# 6v_BOOST.net
KiCad netlist of a schematic drawn in Altium Designer
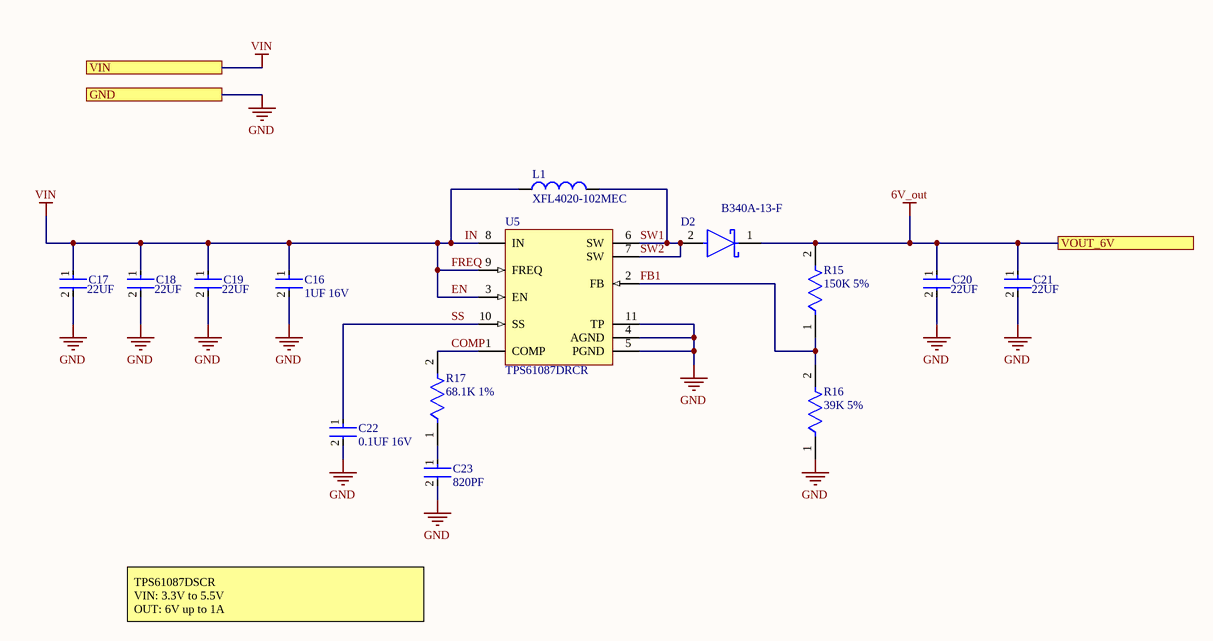
[diagram p0: 6v_BOOST.SchDoc]

(export (version "E")
  (design (tool "Eeschema 10.0.6"))
  (components
    (comp (ref "C16")
      (value "1UF 16V")
      (footprint "FP-CC0603-DA-MFG")
      (description "CC0603 1 uF X7R 10.00% 16 V")
      (fields (field (name "MANUFACTURER") "YAGEO") (field (name "TOLERANCE") "0.1"))
      (libsource (lib "Altium Content Vault") (part "11868f565c42a9108669ba33697ecf6"))
    )
    (comp (ref "C17")
      (value "22UF")
      (footprint "FP-CC0805-0_2-1_45-IPC_C")
      (description "CAP CER 22UF 25V X5R 0805")
      (fields (field (name "TOLERANCE") "20%"))
      (libsource (lib "Altium Content Vault") (part "11868f565c42a9108669ba33697ecf6"))
    )
    (comp (ref "C18")
      (value "22UF")
      (footprint "FP-CC0805-0_2-1_45-IPC_C")
      (description "CAP CER 22UF 25V X5R 0805")
      (fields (field (name "TOLERANCE") "20%"))
      (libsource (lib "Altium Content Vault") (part "11868f565c42a9108669ba33697ecf6"))
    )
    (comp (ref "C19")
      (value "22UF")
      (footprint "FP-CC0805-0_2-1_45-IPC_C")
      (description "CAP CER 22UF 25V X5R 0805")
      (fields (field (name "TOLERANCE") "20%"))
      (libsource (lib "Altium Content Vault") (part "11868f565c42a9108669ba33697ecf6"))
    )
    (comp (ref "C20")
      (value "22UF")
      (footprint "FP-CC0805-0_2-1_45-IPC_C")
      (description "CAP CER 22UF 25V X5R 0805")
      (fields (field (name "TOLERANCE") "20%"))
      (libsource (lib "Altium Content Vault") (part "11868f565c42a9108669ba33697ecf6"))
    )
    (comp (ref "C21")
      (value "22UF")
      (footprint "FP-CC0805-0_2-1_45-IPC_C")
      (description "CAP CER 22UF 25V X5R 0805")
      (fields (field (name "TOLERANCE") "20%"))
      (libsource (lib "Altium Content Vault") (part "11868f565c42a9108669ba33697ecf6"))
    )
    (comp (ref "C22")
      (value "0.1UF 16V")
      (footprint "FP-CC0402-MFG")
      (description "CC0402 100 nF X7R 10.00% 25 V")
      (fields
        (field (name "MANUFACTURER PART NUMBER") "CC0402KPX7R8BB104")
        (field (name "MANUFACTURER") "YAGEO")
      )
      (libsource (lib "Altium Content Vault") (part "11868f565c42a9108669ba33697ecf6"))
    )
    (comp (ref "C23")
      (value "820PF")
      (footprint "FP-CC0402-MFG")
      (description "CAP CER 820PF 50V X7R 0402")
      (fields (field (name "TOLERANCE") "0.1") (field (name "MANUFACTURER PART NUMBER") "CC0402KRX7R9BB821"))
      (libsource (lib "Altium Content Vault") (part "11868f565c42a9108669ba33697ecf6"))
    )
    (comp (ref "D2")
      (value "B340A-13-F")
      (footprint "FP-SMA-MFG")
      (description "DIODE SCHOTTKY 40V 3A SMA")
      (fields (field (name "VOLTAGE") "40V"))
      (libsource (lib "Altium Content Vault") (part "1d6ec82d83fb6aee721767c19dac4b9"))
    )
    (comp (ref "L1")
      (value "XFL4020-102MEC")
      (footprint "COIL-XFL4020_V")
      (description "Shielded Power Inductor, 1 uH, 64 MHz, -40 to 125 degC, 2-Pin SMD, RoHS, Tape and Reel")
      (fields (field (name "MANUFACTURER") "Coilcraft") (field (name "TOLERANCE") "20%"))
      (libsource (lib "Altium Content Vault") (part "IND-2"))
    )
    (comp (ref "R15")
      (value "150K 5%")
      (footprint "FP-RMCF0603-IPC_A")
      (description "150kΩ ±5% 0.1W 0603 Thick Film Chip Resistor AEC-Q200 compliant")
      (fields (field (name "TOLERANCE") "5%"))
      (libsource (lib "Altium Content Vault") (part "1029c3af85768c4190bb7ad29bc67b5"))
    )
    (comp (ref "R16")
      (value "39K 5%")
      (footprint "FP-RMCF0603-IPC_B")
      (description "39kΩ ±5% 0.1W 0603 Thick Film Chip Resistor AEC-Q200 compliant")
      (fields (field (name "TOLERANCE") "5%"))
      (libsource (lib "Altium Content Vault") (part "1029c3af85768c4190bb7ad29bc67b5"))
    )
    (comp (ref "R17")
      (value "68.1K 1%")
      (footprint "FP-RMCF0402-IPC_C")
      (description "68.1kΩ ±1% 0.063W 0402 Thick Film Chip Resistor AEC-Q200 compliant")
      (fields (field (name "TOLERANCE") "1%"))
      (libsource (lib "Altium Content Vault") (part "1029c3af85768c4190bb7ad29bc67b5"))
    )
    (comp (ref "U5")
      (value "TPS61087DRCR")
      (footprint "DRC0010J_V")
      (fields (field (name "MANUFACTURER") "Texas Instruments"))
      (libsource (lib "Altium Content Vault") (part "TI-TPS61087DRC10-2400X1650TP"))
    )
  )
  (nets
    (net (code "1") (name "/COMP") (class "Default")
      (node (ref "R17") (pin "2") (pinfunction "2_2") (pintype "passive"))
      (node (ref "U5") (pin "1") (pinfunction "COMP_1") (pintype "passive"))
    )
    (net (code "2") (name "/FB1") (class "Default")
      (node (ref "R15") (pin "1") (pinfunction "1_1") (pintype "passive"))
      (node (ref "R16") (pin "2") (pinfunction "2_2") (pintype "passive"))
      (node (ref "U5") (pin "2") (pinfunction "FB_2") (pintype "input"))
    )
    (net (code "3") (name "/SS") (class "Default")
      (node (ref "C22") (pin "1") (pinfunction "1_1") (pintype "passive"))
      (node (ref "U5") (pin "10") (pinfunction "SS_10") (pintype "input"))
    )
    (net (code "4") (name "/SW1") (class "Default")
      (node (ref "D2") (pin "2") (pinfunction "A_2") (pintype "passive"))
      (node (ref "L1") (pin "2") (pinfunction "2_2") (pintype "passive"))
      (node (ref "U5") (pin "6") (pinfunction "SW_6") (pintype "power_in"))
      (node (ref "U5") (pin "7") (pinfunction "SW_7") (pintype "power_in"))
    )
    (net (code "5") (name "6V_out") (class "Default")
      (node (ref "C20") (pin "1") (pinfunction "1_1") (pintype "passive"))
      (node (ref "C21") (pin "1") (pinfunction "1_1") (pintype "passive"))
      (node (ref "D2") (pin "1") (pinfunction "C_1") (pintype "passive"))
      (node (ref "R15") (pin "2") (pinfunction "2_2") (pintype "passive"))
    )
    (net (code "6") (name "GND") (class "Default")
      (node (ref "C16") (pin "2") (pinfunction "2_2") (pintype "passive"))
      (node (ref "C17") (pin "2") (pinfunction "2_2") (pintype "passive"))
      (node (ref "C18") (pin "2") (pinfunction "2_2") (pintype "passive"))
      (node (ref "C19") (pin "2") (pinfunction "2_2") (pintype "passive"))
      (node (ref "C20") (pin "2") (pinfunction "2_2") (pintype "passive"))
      (node (ref "C21") (pin "2") (pinfunction "2_2") (pintype "passive"))
      (node (ref "C22") (pin "2") (pinfunction "2_2") (pintype "passive"))
      (node (ref "C23") (pin "2") (pinfunction "2_2") (pintype "passive"))
      (node (ref "R16") (pin "1") (pinfunction "1_1") (pintype "passive"))
      (node (ref "U5") (pin "11") (pinfunction "TP_11") (pintype "power_in"))
      (node (ref "U5") (pin "4") (pinfunction "AGND_4") (pintype "power_in"))
      (node (ref "U5") (pin "5") (pinfunction "PGND_5") (pintype "power_in"))
    )
    (net (code "7") (name "Net-(C23-Pad1)") (class "Default")
      (node (ref "C23") (pin "1") (pinfunction "1_1") (pintype "passive"))
      (node (ref "R17") (pin "1") (pinfunction "1_1") (pintype "passive"))
    )
    (net (code "8") (name "VIN") (class "Default")
      (node (ref "C16") (pin "1") (pinfunction "1_1") (pintype "passive"))
      (node (ref "C17") (pin "1") (pinfunction "1_1") (pintype "passive"))
      (node (ref "C18") (pin "1") (pinfunction "1_1") (pintype "passive"))
      (node (ref "C19") (pin "1") (pinfunction "1_1") (pintype "passive"))
      (node (ref "L1") (pin "1") (pinfunction "1_1") (pintype "passive"))
      (node (ref "U5") (pin "3") (pinfunction "EN_3") (pintype "input"))
      (node (ref "U5") (pin "8") (pinfunction "IN_8") (pintype "power_in"))
      (node (ref "U5") (pin "9") (pinfunction "FREQ_9") (pintype "input"))
    )
  )
)
